# Connectors.net
KiCad netlist of a schematic drawn in Altium Designer
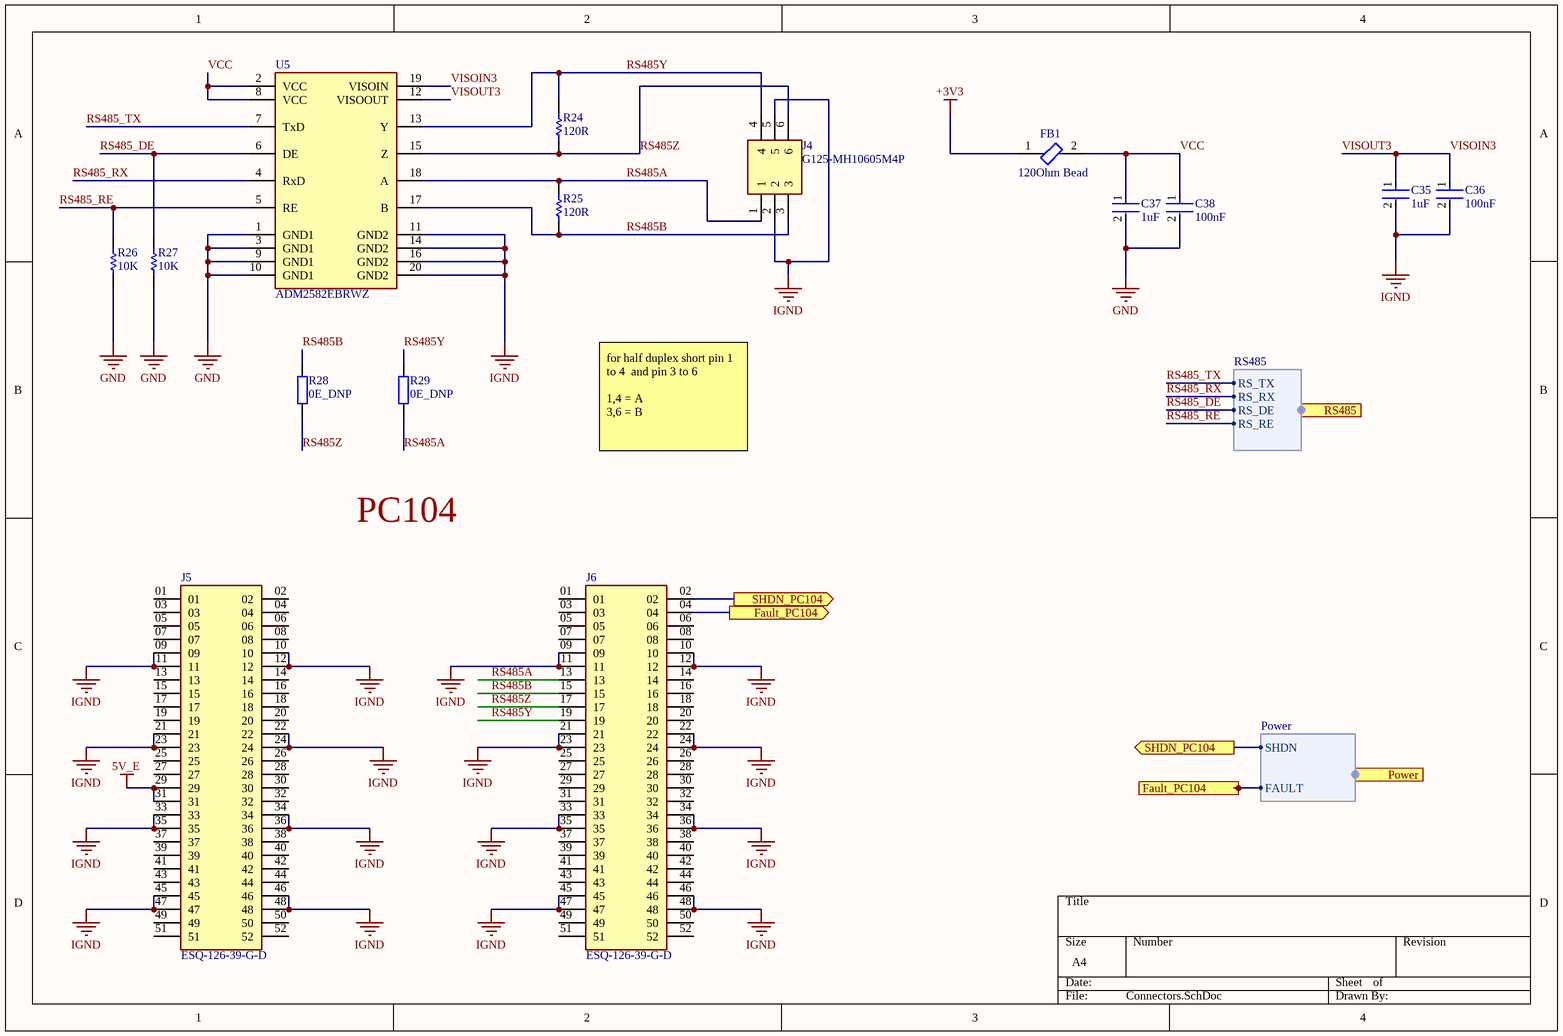
[diagram p0: Connectors.SchDoc]

(export (version "E")
  (design (tool "Eeschema 10.0.6"))
  (components
    (comp (ref "C35")
      (value "1uF")
      (footprint "CAP0603S")
      (description "Ceramic Capacitor General Use 1uF ±10% 50V X7R 0603")
      (fields (field (name "TOLERANCE") "10%"))
      (libsource (lib "Miscellaneous Devices") (part "11868f565c42a9108669ba33697ecf6"))
    )
    (comp (ref "C36")
      (value "100nF")
      (footprint "CAP0402S")
      (description "CAP CER 0.1UF 10V X5R 0402")
      (fields (field (name "MANUFACTURER") "Kemet") (field (name "TOLERANCE") "0.1"))
      (libsource (lib "Miscellaneous Devices") (part "b4654b650e69147ec39a6b967a45e02"))
    )
    (comp (ref "C37")
      (value "1uF")
      (footprint "CAP0603S")
      (description "Ceramic Capacitor General Use 1uF ±10% 50V X7R 0603")
      (fields (field (name "TOLERANCE") "10%"))
      (libsource (lib "Miscellaneous Devices") (part "11868f565c42a9108669ba33697ecf6"))
    )
    (comp (ref "C38")
      (value "100nF")
      (footprint "CAP0402S")
      (description "CAP CER 0.1UF 10V X5R 0402")
      (fields (field (name "MANUFACTURER") "Kemet") (field (name "TOLERANCE") "0.1"))
      (libsource (lib "Miscellaneous Devices") (part "b4654b650e69147ec39a6b967a45e02"))
    )
    (comp (ref "FB1")
      (value "120Ohm Bead")
      (footprint "FB0402S")
      (description "FERRITE BEAD 120 OHM 0805 1LN")
      (fields (field (name "TOLERANCE") "25%"))
      (libsource (lib "Miscellaneous Devices") (part "5f30dd21d616792df468990f7003faa"))
    )
    (comp (ref "J4")
      (value "G125-MH10605M4P")
      (footprint "HARWIN_G125-MH10605M4P")
      (description "Connector")
      (fields (field (name "MOUSER PART NUMBER") "855-G125MH1065M4PM4P"))
      (libsource (lib "SamacSys") (part "G125-MH10605M4P"))
    )
    (comp (ref "J5")
      (value "ESQ-126-39-G-D")
      (footprint "SAMTEC_ESQ-126-39-G-D")
      (description "52 Position Elevated Socket Connector Through Hole")
      (fields (field (name "MF") "Samtec"))
      (libsource (lib "SnapEDAsch") (part "ESQ-126-39-G-D"))
    )
    (comp (ref "J6")
      (value "ESQ-126-39-G-D")
      (footprint "SAMTEC_ESQ-126-39-G-D")
      (description "52 Position Elevated Socket Connector Through Hole")
      (fields (field (name "MF") "Samtec"))
      (libsource (lib "SnapEDAsch") (part "ESQ-126-39-G-D"))
    )
    (comp (ref "R24")
      (value "120R")
      (footprint "RES0805S")
      (description "Chip Resistor, 120 Ohm, +/- 1%, 0.125 W, -55 to 155 degC, 0805 (2012 Metric), RoHS, Tape and Reel")
      (fields (field (name "MANUFACTURER") "Panasonic"))
      (libsource (lib "Miscellaneous Devices") (part "RES-2"))
    )
    (comp (ref "R25")
      (value "120R")
      (footprint "RES0805S")
      (description "Chip Resistor, 120 Ohm, +/- 1%, 0.125 W, -55 to 155 degC, 0805 (2012 Metric), RoHS, Tape and Reel")
      (fields (field (name "MANUFACTURER") "Panasonic"))
      (libsource (lib "Miscellaneous Devices") (part "RES-2"))
    )
    (comp (ref "R26")
      (value "10K")
      (footprint "RES0402S")
      (description "Chip Resistor, 10 KOhm, +/- 1%, 0.1 W, -55 to 155 degC, 0402 (1005 Metric), RoHS, Tape and Reel")
      (fields (field (name "TOLERANCE") "1%") (field (name "MANUFACTURER") "Panasonic"))
      (libsource (lib "Miscellaneous Devices") (part "RES-2"))
    )
    (comp (ref "R27")
      (value "10K")
      (footprint "RES0402S")
      (description "Chip Resistor, 10 KOhm, +/- 1%, 0.1 W, -55 to 155 degC, 0402 (1005 Metric), RoHS, Tape and Reel")
      (fields (field (name "TOLERANCE") "1%") (field (name "MANUFACTURER") "Panasonic"))
      (libsource (lib "Miscellaneous Devices") (part "RES-2"))
    )
    (comp (ref "R28")
      (value "0E_DNP")
      (footprint "RES0603S")
      (description "Resistor SMD 0603")
      (libsource (lib "Schematic-Lib-PhilsLab") (part "RES_0603"))
    )
    (comp (ref "R29")
      (value "0E_DNP")
      (footprint "RES0603S")
      (description "Resistor SMD 0603")
      (libsource (lib "Schematic-Lib-PhilsLab") (part "RES_0603"))
    )
    (comp (ref "U5")
      (value "ADM2582EBRWZ")
      (footprint "SOIC-20")
      (description "Isolated Full Duplex RS485 Transreciver")
      (libsource (lib "TM2S") (part "ADM2582EBRWZ"))
    )
  )
  (nets
    (net (code "3") (name "+3V3") (class "Default")
      (node (ref "FB1") (pin "1") (pinfunction "1_1") (pintype "passive"))
    )
    (net (code "4") (name "/Fault_PC104") (class "Default")
      (node (ref "J6") (pin "04") (pinfunction "04_04") (pintype "passive"))
    )
    (net (code "5") (name "/RS485A") (class "Default")
      (node (ref "J4") (pin "1") (pinfunction "1_1") (pintype "passive"))
      (node (ref "J6") (pin "13") (pinfunction "13_13") (pintype "passive"))
      (node (ref "R25") (pin "2") (pinfunction "2_2") (pintype "passive"))
      (node (ref "R29") (pin "1") (pinfunction "1_1") (pintype "passive"))
      (node (ref "U5") (pin "18") (pinfunction "A_18") (pintype "passive"))
    )
    (net (code "6") (name "/RS485B") (class "Default")
      (node (ref "J4") (pin "3") (pinfunction "3_3") (pintype "passive"))
      (node (ref "J6") (pin "15") (pinfunction "15_15") (pintype "passive"))
      (node (ref "R25") (pin "1") (pinfunction "1_1") (pintype "passive"))
      (node (ref "R28") (pin "2") (pinfunction "2_2") (pintype "passive"))
      (node (ref "U5") (pin "17") (pinfunction "B_17") (pintype "passive"))
    )
    (net (code "7") (name "/RS485Y") (class "Default")
      (node (ref "J4") (pin "4") (pinfunction "4_4") (pintype "passive"))
      (node (ref "J6") (pin "19") (pinfunction "19_19") (pintype "passive"))
      (node (ref "R24") (pin "2") (pinfunction "2_2") (pintype "passive"))
      (node (ref "R29") (pin "2") (pinfunction "2_2") (pintype "passive"))
      (node (ref "U5") (pin "13") (pinfunction "Y_13") (pintype "passive"))
    )
    (net (code "8") (name "/RS485Z") (class "Default")
      (node (ref "J4") (pin "6") (pinfunction "6_6") (pintype "passive"))
      (node (ref "J6") (pin "17") (pinfunction "17_17") (pintype "passive"))
      (node (ref "R24") (pin "1") (pinfunction "1_1") (pintype "passive"))
      (node (ref "R28") (pin "1") (pinfunction "1_1") (pintype "passive"))
      (node (ref "U5") (pin "15") (pinfunction "Z_15") (pintype "passive"))
    )
    (net (code "9") (name "/RS485_DE") (class "Default")
      (node (ref "R27") (pin "2") (pinfunction "2_2") (pintype "passive"))
      (node (ref "U5") (pin "6") (pinfunction "DE_6") (pintype "passive"))
    )
    (net (code "10") (name "/RS485_RE") (class "Default")
      (node (ref "R26") (pin "2") (pinfunction "2_2") (pintype "passive"))
      (node (ref "U5") (pin "5") (pinfunction "RE_5") (pintype "passive"))
    )
    (net (code "11") (name "/RS485_RX") (class "Default")
      (node (ref "U5") (pin "4") (pinfunction "RxD_4") (pintype "passive"))
    )
    (net (code "12") (name "/RS485_TX") (class "Default")
      (node (ref "U5") (pin "7") (pinfunction "TxD_7") (pintype "passive"))
    )
    (net (code "13") (name "/SHDN_PC104") (class "Default")
      (node (ref "J6") (pin "02") (pinfunction "02_02") (pintype "passive"))
    )
    (net (code "14") (name "/VCC") (class "Default")
      (node (ref "C37") (pin "1") (pinfunction "1_1") (pintype "passive"))
      (node (ref "C38") (pin "1") (pinfunction "1_1") (pintype "passive"))
      (node (ref "FB1") (pin "2") (pinfunction "2_2") (pintype "passive"))
      (node (ref "U5") (pin "2") (pinfunction "VCC_2") (pintype "passive"))
      (node (ref "U5") (pin "8") (pinfunction "VCC_8") (pintype "passive"))
    )
    (net (code "15") (name "/VISOIN3") (class "Default")
      (node (ref "C35") (pin "1") (pinfunction "1_1") (pintype "passive"))
      (node (ref "C36") (pin "1") (pinfunction "1_1") (pintype "passive"))
      (node (ref "U5") (pin "12") (pinfunction "VISOOUT_12") (pintype "passive"))
      (node (ref "U5") (pin "19") (pinfunction "VISOIN_19") (pintype "passive"))
    )
    (net (code "18") (name "5V_E") (class "Default")
      (node (ref "J5") (pin "29") (pinfunction "29_29") (pintype "passive"))
      (node (ref "J5") (pin "31") (pinfunction "31_31") (pintype "passive"))
    )
    (net (code "19") (name "GND") (class "Default")
      (node (ref "C37") (pin "2") (pinfunction "2_2") (pintype "passive"))
      (node (ref "C38") (pin "2") (pinfunction "2_2") (pintype "passive"))
      (node (ref "R26") (pin "1") (pinfunction "1_1") (pintype "passive"))
      (node (ref "R27") (pin "1") (pinfunction "1_1") (pintype "passive"))
      (node (ref "U5") (pin "1") (pinfunction "GND1_1") (pintype "passive"))
      (node (ref "U5") (pin "10") (pinfunction "GND1_10") (pintype "passive"))
      (node (ref "U5") (pin "3") (pinfunction "GND1_3") (pintype "passive"))
      (node (ref "U5") (pin "9") (pinfunction "GND1_9") (pintype "passive"))
    )
    (net (code "20") (name "IGND") (class "Default")
      (node (ref "C35") (pin "2") (pinfunction "2_2") (pintype "passive"))
      (node (ref "C36") (pin "2") (pinfunction "2_2") (pintype "passive"))
      (node (ref "J4") (pin "2") (pinfunction "2_2") (pintype "passive"))
      (node (ref "J4") (pin "5") (pinfunction "5_5") (pintype "passive"))
      (node (ref "J5") (pin "09") (pinfunction "09_09") (pintype "passive"))
      (node (ref "J5") (pin "10") (pinfunction "10_10") (pintype "passive"))
      (node (ref "J5") (pin "11") (pinfunction "11_11") (pintype "passive"))
      (node (ref "J5") (pin "12") (pinfunction "12_12") (pintype "passive"))
      (node (ref "J5") (pin "21") (pinfunction "21_21") (pintype "passive"))
      (node (ref "J5") (pin "22") (pinfunction "22_22") (pintype "passive"))
      (node (ref "J5") (pin "23") (pinfunction "23_23") (pintype "passive"))
      (node (ref "J5") (pin "24") (pinfunction "24_24") (pintype "passive"))
      (node (ref "J5") (pin "33") (pinfunction "33_33") (pintype "passive"))
      (node (ref "J5") (pin "34") (pinfunction "34_34") (pintype "passive"))
      (node (ref "J5") (pin "35") (pinfunction "35_35") (pintype "passive"))
      (node (ref "J5") (pin "36") (pinfunction "36_36") (pintype "passive"))
      (node (ref "J5") (pin "45") (pinfunction "45_45") (pintype "passive"))
      (node (ref "J5") (pin "46") (pinfunction "46_46") (pintype "passive"))
      (node (ref "J5") (pin "47") (pinfunction "47_47") (pintype "passive"))
      (node (ref "J5") (pin "48") (pinfunction "48_48") (pintype "passive"))
      (node (ref "J6") (pin "09") (pinfunction "09_09") (pintype "passive"))
      (node (ref "J6") (pin "10") (pinfunction "10_10") (pintype "passive"))
      (node (ref "J6") (pin "11") (pinfunction "11_11") (pintype "passive"))
      (node (ref "J6") (pin "12") (pinfunction "12_12") (pintype "passive"))
      (node (ref "J6") (pin "21") (pinfunction "21_21") (pintype "passive"))
      (node (ref "J6") (pin "22") (pinfunction "22_22") (pintype "passive"))
      (node (ref "J6") (pin "23") (pinfunction "23_23") (pintype "passive"))
      (node (ref "J6") (pin "24") (pinfunction "24_24") (pintype "passive"))
      (node (ref "J6") (pin "33") (pinfunction "33_33") (pintype "passive"))
      (node (ref "J6") (pin "34") (pinfunction "34_34") (pintype "passive"))
      (node (ref "J6") (pin "35") (pinfunction "35_35") (pintype "passive"))
      (node (ref "J6") (pin "36") (pinfunction "36_36") (pintype "passive"))
      (node (ref "J6") (pin "45") (pinfunction "45_45") (pintype "passive"))
      (node (ref "J6") (pin "46") (pinfunction "46_46") (pintype "passive"))
      (node (ref "J6") (pin "47") (pinfunction "47_47") (pintype "passive"))
      (node (ref "J6") (pin "48") (pinfunction "48_48") (pintype "passive"))
      (node (ref "U5") (pin "11") (pinfunction "GND2_11") (pintype "passive"))
      (node (ref "U5") (pin "14") (pinfunction "GND2_14") (pintype "passive"))
      (node (ref "U5") (pin "16") (pinfunction "GND2_16") (pintype "passive"))
      (node (ref "U5") (pin "20") (pinfunction "GND2_20") (pintype "passive"))
    )
    (net (code "21") (name "unconnected-(J5-Pad01)") (class "Default")
      (node (ref "J5") (pin "01") (pinfunction "01_01") (pintype "passive"))
    )
    (net (code "22") (name "unconnected-(J5-Pad02)") (class "Default")
      (node (ref "J5") (pin "02") (pinfunction "02_02") (pintype "passive"))
    )
    (net (code "23") (name "unconnected-(J5-Pad03)") (class "Default")
      (node (ref "J5") (pin "03") (pinfunction "03_03") (pintype "passive"))
    )
    (net (code "24") (name "unconnected-(J5-Pad04)") (class "Default")
      (node (ref "J5") (pin "04") (pinfunction "04_04") (pintype "passive"))
    )
    (net (code "25") (name "unconnected-(J5-Pad05)") (class "Default")
      (node (ref "J5") (pin "05") (pinfunction "05_05") (pintype "passive"))
    )
    (net (code "26") (name "unconnected-(J5-Pad06)") (class "Default")
      (node (ref "J5") (pin "06") (pinfunction "06_06") (pintype "passive"))
    )
    (net (code "27") (name "unconnected-(J5-Pad07)") (class "Default")
      (node (ref "J5") (pin "07") (pinfunction "07_07") (pintype "passive"))
    )
    (net (code "28") (name "unconnected-(J5-Pad08)") (class "Default")
      (node (ref "J5") (pin "08") (pinfunction "08_08") (pintype "passive"))
    )
    (net (code "29") (name "unconnected-(J5-Pad13)") (class "Default")
      (node (ref "J5") (pin "13") (pinfunction "13_13") (pintype "passive"))
    )
    (net (code "30") (name "unconnected-(J5-Pad14)") (class "Default")
      (node (ref "J5") (pin "14") (pinfunction "14_14") (pintype "passive"))
    )
    (net (code "31") (name "unconnected-(J5-Pad15)") (class "Default")
      (node (ref "J5") (pin "15") (pinfunction "15_15") (pintype "passive"))
    )
    (net (code "32") (name "unconnected-(J5-Pad16)") (class "Default")
      (node (ref "J5") (pin "16") (pinfunction "16_16") (pintype "passive"))
    )
    (net (code "33") (name "unconnected-(J5-Pad17)") (class "Default")
      (node (ref "J5") (pin "17") (pinfunction "17_17") (pintype "passive"))
    )
    (net (code "34") (name "unconnected-(J5-Pad18)") (class "Default")
      (node (ref "J5") (pin "18") (pinfunction "18_18") (pintype "passive"))
    )
    (net (code "35") (name "unconnected-(J5-Pad19)") (class "Default")
      (node (ref "J5") (pin "19") (pinfunction "19_19") (pintype "passive"))
    )
    (net (code "36") (name "unconnected-(J5-Pad20)") (class "Default")
      (node (ref "J5") (pin "20") (pinfunction "20_20") (pintype "passive"))
    )
    (net (code "37") (name "unconnected-(J5-Pad25)") (class "Default")
      (node (ref "J5") (pin "25") (pinfunction "25_25") (pintype "passive"))
    )
    (net (code "38") (name "unconnected-(J5-Pad26)") (class "Default")
      (node (ref "J5") (pin "26") (pinfunction "26_26") (pintype "passive"))
    )
    (net (code "39") (name "unconnected-(J5-Pad27)") (class "Default")
      (node (ref "J5") (pin "27") (pinfunction "27_27") (pintype "passive"))
    )
    (net (code "40") (name "unconnected-(J5-Pad28)") (class "Default")
      (node (ref "J5") (pin "28") (pinfunction "28_28") (pintype "passive"))
    )
    (net (code "41") (name "unconnected-(J5-Pad30)") (class "Default")
      (node (ref "J5") (pin "30") (pinfunction "30_30") (pintype "passive"))
    )
    (net (code "42") (name "unconnected-(J5-Pad32)") (class "Default")
      (node (ref "J5") (pin "32") (pinfunction "32_32") (pintype "passive"))
    )
    (net (code "43") (name "unconnected-(J5-Pad37)") (class "Default")
      (node (ref "J5") (pin "37") (pinfunction "37_37") (pintype "passive"))
    )
    (net (code "44") (name "unconnected-(J5-Pad38)") (class "Default")
      (node (ref "J5") (pin "38") (pinfunction "38_38") (pintype "passive"))
    )
    (net (code "45") (name "unconnected-(J5-Pad39)") (class "Default")
      (node (ref "J5") (pin "39") (pinfunction "39_39") (pintype "passive"))
    )
    (net (code "46") (name "unconnected-(J5-Pad40)") (class "Default")
      (node (ref "J5") (pin "40") (pinfunction "40_40") (pintype "passive"))
    )
    (net (code "47") (name "unconnected-(J5-Pad41)") (class "Default")
      (node (ref "J5") (pin "41") (pinfunction "41_41") (pintype "passive"))
    )
    (net (code "48") (name "unconnected-(J5-Pad42)") (class "Default")
      (node (ref "J5") (pin "42") (pinfunction "42_42") (pintype "passive"))
    )
    (net (code "49") (name "unconnected-(J5-Pad43)") (class "Default")
      (node (ref "J5") (pin "43") (pinfunction "43_43") (pintype "passive"))
    )
    (net (code "50") (name "unconnected-(J5-Pad44)") (class "Default")
      (node (ref "J5") (pin "44") (pinfunction "44_44") (pintype "passive"))
    )
    (net (code "51") (name "unconnected-(J5-Pad49)") (class "Default")
      (node (ref "J5") (pin "49") (pinfunction "49_49") (pintype "passive"))
    )
    (net (code "52") (name "unconnected-(J5-Pad50)") (class "Default")
      (node (ref "J5") (pin "50") (pinfunction "50_50") (pintype "passive"))
    )
    (net (code "53") (name "unconnected-(J5-Pad51)") (class "Default")
      (node (ref "J5") (pin "51") (pinfunction "51_51") (pintype "passive"))
    )
    (net (code "54") (name "unconnected-(J5-Pad52)") (class "Default")
      (node (ref "J5") (pin "52") (pinfunction "52_52") (pintype "passive"))
    )
    (net (code "55") (name "unconnected-(J6-Pad01)") (class "Default")
      (node (ref "J6") (pin "01") (pinfunction "01_01") (pintype "passive"))
    )
    (net (code "56") (name "unconnected-(J6-Pad03)") (class "Default")
      (node (ref "J6") (pin "03") (pinfunction "03_03") (pintype "passive"))
    )
    (net (code "57") (name "unconnected-(J6-Pad05)") (class "Default")
      (node (ref "J6") (pin "05") (pinfunction "05_05") (pintype "passive"))
    )
    (net (code "58") (name "unconnected-(J6-Pad06)") (class "Default")
      (node (ref "J6") (pin "06") (pinfunction "06_06") (pintype "passive"))
    )
    (net (code "59") (name "unconnected-(J6-Pad07)") (class "Default")
      (node (ref "J6") (pin "07") (pinfunction "07_07") (pintype "passive"))
    )
    (net (code "60") (name "unconnected-(J6-Pad08)") (class "Default")
      (node (ref "J6") (pin "08") (pinfunction "08_08") (pintype "passive"))
    )
    (net (code "61") (name "unconnected-(J6-Pad14)") (class "Default")
      (node (ref "J6") (pin "14") (pinfunction "14_14") (pintype "passive"))
    )
    (net (code "62") (name "unconnected-(J6-Pad16)") (class "Default")
      (node (ref "J6") (pin "16") (pinfunction "16_16") (pintype "passive"))
    )
    (net (code "63") (name "unconnected-(J6-Pad18)") (class "Default")
      (node (ref "J6") (pin "18") (pinfunction "18_18") (pintype "passive"))
    )
    (net (code "64") (name "unconnected-(J6-Pad20)") (class "Default")
      (node (ref "J6") (pin "20") (pinfunction "20_20") (pintype "passive"))
    )
    (net (code "65") (name "unconnected-(J6-Pad25)") (class "Default")
      (node (ref "J6") (pin "25") (pinfunction "25_25") (pintype "passive"))
    )
    (net (code "66") (name "unconnected-(J6-Pad26)") (class "Default")
      (node (ref "J6") (pin "26") (pinfunction "26_26") (pintype "passive"))
    )
    (net (code "67") (name "unconnected-(J6-Pad27)") (class "Default")
      (node (ref "J6") (pin "27") (pinfunction "27_27") (pintype "passive"))
    )
    (net (code "68") (name "unconnected-(J6-Pad28)") (class "Default")
      (node (ref "J6") (pin "28") (pinfunction "28_28") (pintype "passive"))
    )
    (net (code "69") (name "unconnected-(J6-Pad29)") (class "Default")
      (node (ref "J6") (pin "29") (pinfunction "29_29") (pintype "passive"))
    )
    (net (code "70") (name "unconnected-(J6-Pad30)") (class "Default")
      (node (ref "J6") (pin "30") (pinfunction "30_30") (pintype "passive"))
    )
    (net (code "71") (name "unconnected-(J6-Pad31)") (class "Default")
      (node (ref "J6") (pin "31") (pinfunction "31_31") (pintype "passive"))
    )
    (net (code "72") (name "unconnected-(J6-Pad32)") (class "Default")
      (node (ref "J6") (pin "32") (pinfunction "32_32") (pintype "passive"))
    )
    (net (code "73") (name "unconnected-(J6-Pad37)") (class "Default")
      (node (ref "J6") (pin "37") (pinfunction "37_37") (pintype "passive"))
    )
    (net (code "74") (name "unconnected-(J6-Pad38)") (class "Default")
      (node (ref "J6") (pin "38") (pinfunction "38_38") (pintype "passive"))
    )
    (net (code "75") (name "unconnected-(J6-Pad39)") (class "Default")
      (node (ref "J6") (pin "39") (pinfunction "39_39") (pintype "passive"))
    )
    (net (code "76") (name "unconnected-(J6-Pad40)") (class "Default")
      (node (ref "J6") (pin "40") (pinfunction "40_40") (pintype "passive"))
    )
    (net (code "77") (name "unconnected-(J6-Pad41)") (class "Default")
      (node (ref "J6") (pin "41") (pinfunction "41_41") (pintype "passive"))
    )
    (net (code "78") (name "unconnected-(J6-Pad42)") (class "Default")
      (node (ref "J6") (pin "42") (pinfunction "42_42") (pintype "passive"))
    )
    (net (code "79") (name "unconnected-(J6-Pad43)") (class "Default")
      (node (ref "J6") (pin "43") (pinfunction "43_43") (pintype "passive"))
    )
    (net (code "80") (name "unconnected-(J6-Pad44)") (class "Default")
      (node (ref "J6") (pin "44") (pinfunction "44_44") (pintype "passive"))
    )
    (net (code "81") (name "unconnected-(J6-Pad49)") (class "Default")
      (node (ref "J6") (pin "49") (pinfunction "49_49") (pintype "passive"))
    )
    (net (code "82") (name "unconnected-(J6-Pad50)") (class "Default")
      (node (ref "J6") (pin "50") (pinfunction "50_50") (pintype "passive"))
    )
    (net (code "83") (name "unconnected-(J6-Pad51)") (class "Default")
      (node (ref "J6") (pin "51") (pinfunction "51_51") (pintype "passive"))
    )
    (net (code "84") (name "unconnected-(J6-Pad52)") (class "Default")
      (node (ref "J6") (pin "52") (pinfunction "52_52") (pintype "passive"))
    )
  )
)
